# Filter_Capacitors_-_Master_ICSP.net
KiCad netlist of a schematic drawn in Altium Designer
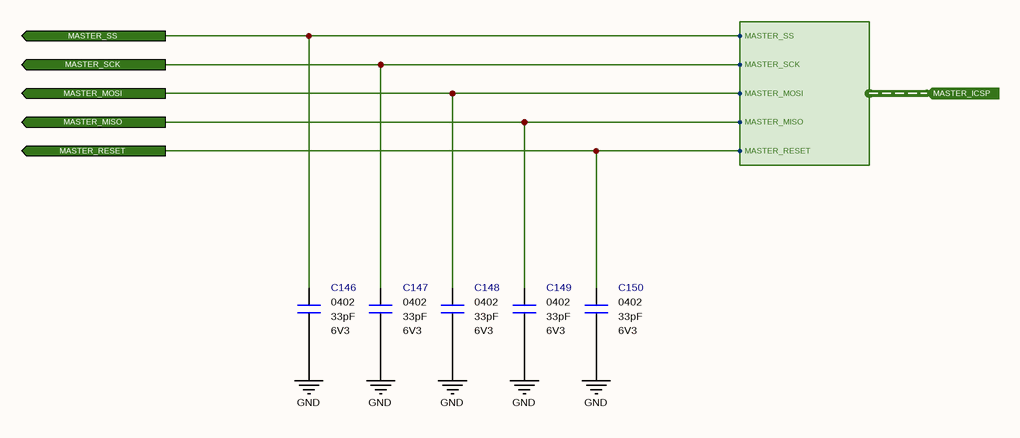
[diagram p0: Filter Capacitors - Master ICSP.SchDoc]

(export (version "E")
  (design (tool "Eeschema 10.0.6"))
  (components
    (comp (ref "C146")
      (value "33pF")
      (footprint "CAPACITOR_0402")
      (description "Capacitor - 33pF [0402] (Ceramic)")
      (fields
        (field (name "TOLERANCE") "10%")
        (field (name "CASE") "0402")
        (field (name "VOLTAGE") "6V3")
        (field (name "MANUFACTURER PART NUMBER") "C0402C330J9RACAUTO")
      )
      (libsource (lib "Ovoo_Library") (part "Capacitor - 33pF [0402-6V3]"))
    )
    (comp (ref "C147")
      (value "33pF")
      (footprint "CAPACITOR_0402")
      (description "Capacitor - 33pF [0402] (Ceramic)")
      (fields
        (field (name "TOLERANCE") "10%")
        (field (name "CASE") "0402")
        (field (name "VOLTAGE") "6V3")
        (field (name "MANUFACTURER PART NUMBER") "C0402C330J9RACAUTO")
      )
      (libsource (lib "Ovoo_Library") (part "Capacitor - 33pF [0402-6V3]"))
    )
    (comp (ref "C148")
      (value "33pF")
      (footprint "CAPACITOR_0402")
      (description "Capacitor - 33pF [0402] (Ceramic)")
      (fields
        (field (name "TOLERANCE") "10%")
        (field (name "CASE") "0402")
        (field (name "VOLTAGE") "6V3")
        (field (name "MANUFACTURER PART NUMBER") "C0402C330J9RACAUTO")
      )
      (libsource (lib "Ovoo_Library") (part "Capacitor - 33pF [0402-6V3]"))
    )
    (comp (ref "C149")
      (value "33pF")
      (footprint "CAPACITOR_0402")
      (description "Capacitor - 33pF [0402] (Ceramic)")
      (fields
        (field (name "TOLERANCE") "10%")
        (field (name "CASE") "0402")
        (field (name "VOLTAGE") "6V3")
        (field (name "MANUFACTURER PART NUMBER") "C0402C330J9RACAUTO")
      )
      (libsource (lib "Ovoo_Library") (part "Capacitor - 33pF [0402-6V3]"))
    )
    (comp (ref "C150")
      (value "33pF")
      (footprint "CAPACITOR_0402")
      (description "Capacitor - 33pF [0402] (Ceramic)")
      (fields
        (field (name "TOLERANCE") "10%")
        (field (name "CASE") "0402")
        (field (name "VOLTAGE") "6V3")
        (field (name "MANUFACTURER PART NUMBER") "C0402C330J9RACAUTO")
      )
      (libsource (lib "Ovoo_Library") (part "Capacitor - 33pF [0402-6V3]"))
    )
  )
  (nets
    (net (code "2") (name "/MASTER_MISO") (class "Default")
      (node (ref "C149") (pin "2") (pinfunction "2_2") (pintype "passive"))
    )
    (net (code "3") (name "/MASTER_MOSI") (class "Default")
      (node (ref "C148") (pin "2") (pinfunction "2_2") (pintype "passive"))
    )
    (net (code "4") (name "/MASTER_RESET") (class "Default")
      (node (ref "C150") (pin "2") (pinfunction "2_2") (pintype "passive"))
    )
    (net (code "5") (name "/MASTER_SCK") (class "Default")
      (node (ref "C147") (pin "2") (pinfunction "2_2") (pintype "passive"))
    )
    (net (code "6") (name "/MASTER_SS") (class "Default")
      (node (ref "C146") (pin "2") (pinfunction "2_2") (pintype "passive"))
    )
    (net (code "8") (name "GND") (class "Default")
      (node (ref "C146") (pin "1") (pinfunction "1_1") (pintype "passive"))
      (node (ref "C147") (pin "1") (pinfunction "1_1") (pintype "passive"))
      (node (ref "C148") (pin "1") (pinfunction "1_1") (pintype "passive"))
      (node (ref "C149") (pin "1") (pinfunction "1_1") (pintype "passive"))
      (node (ref "C150") (pin "1") (pinfunction "1_1") (pintype "passive"))
    )
  )
)
